# SmartHomeControllerCircuit.net
KiCad netlist of a schematic drawn in EAGLE
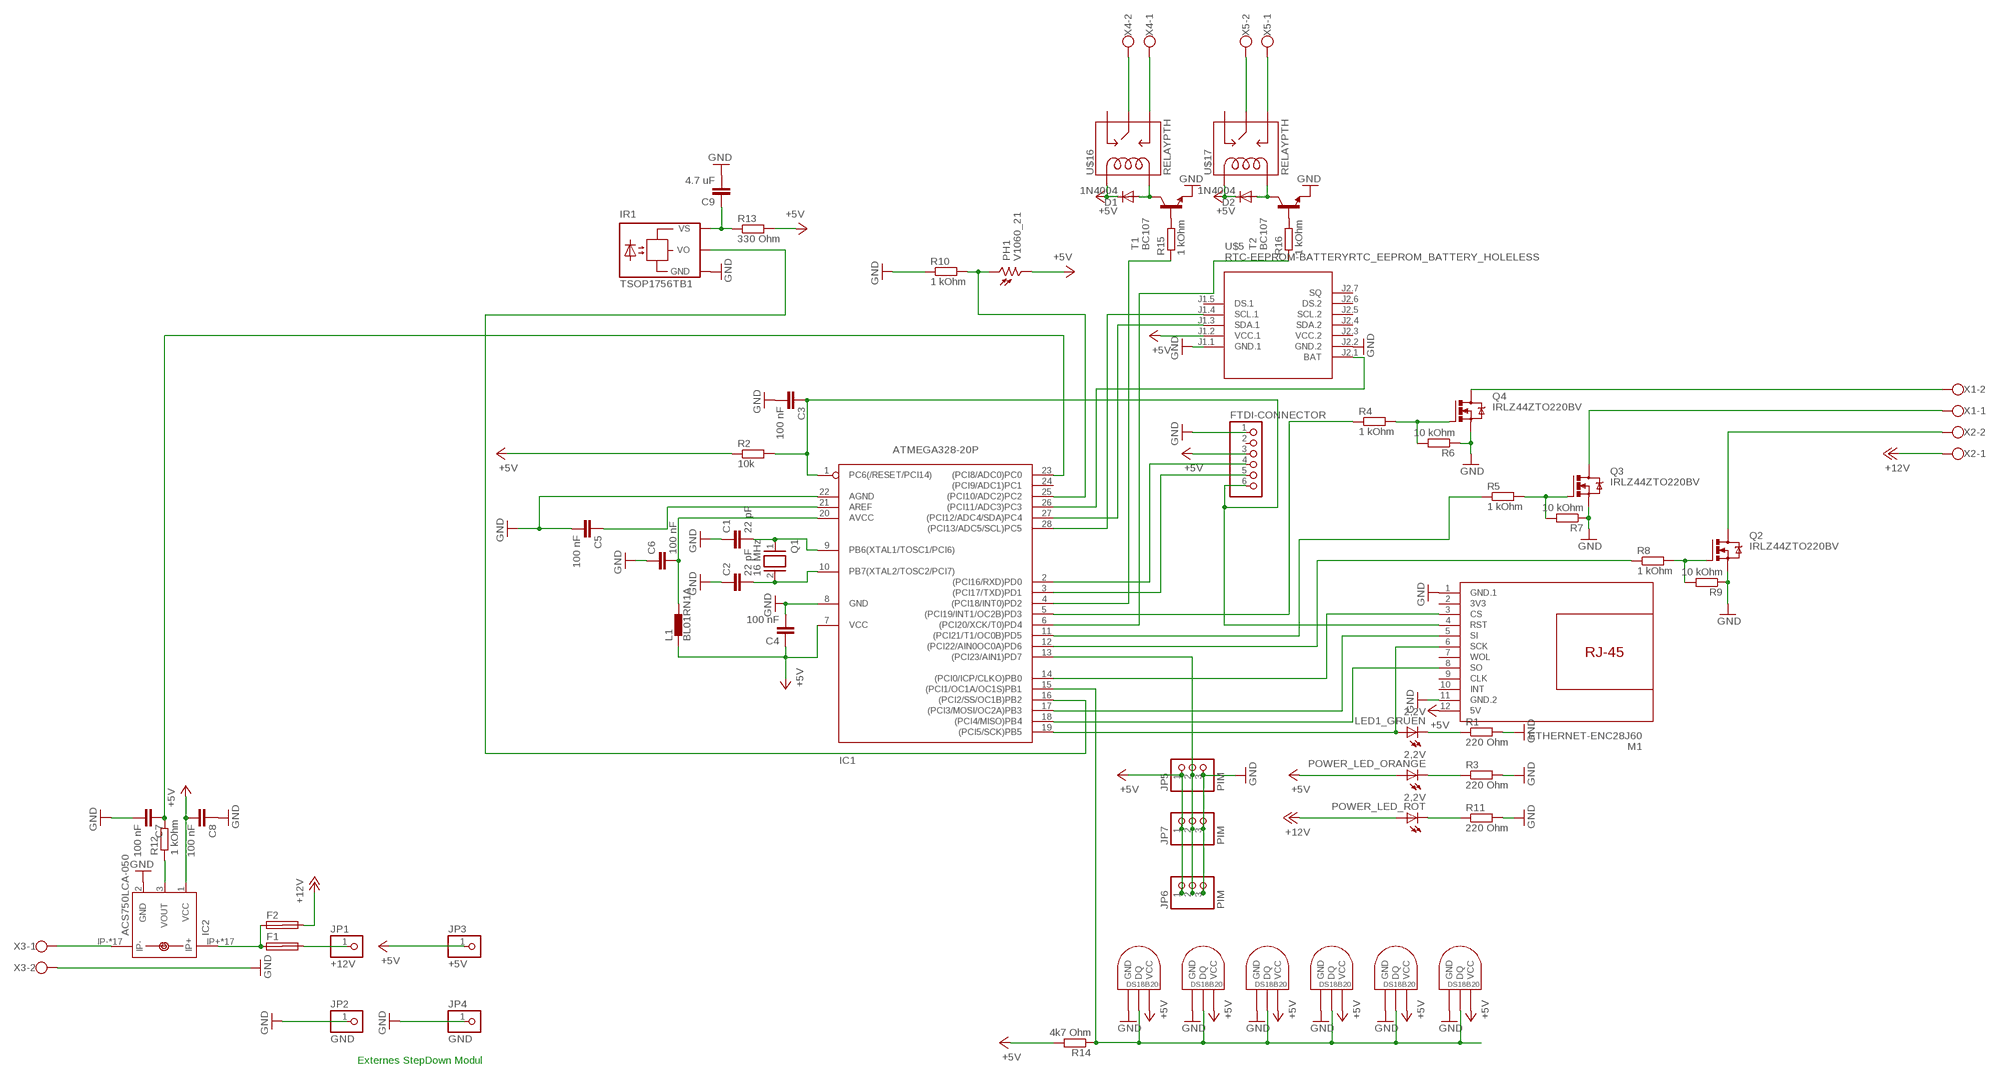
[diagram p0: schematic, sheet 1]

(export (version "E")
  (design (tool "Eeschema 10.0.6"))
  (components
    (comp (ref "C1")
      (value "22 pF")
      (footprint "eagle-import:C050-024X044")
      (libsource (lib "eagle-import") (part "C-EU050-024X044"))
    )
    (comp (ref "C2")
      (value "22 pF")
      (footprint "eagle-import:C050-024X044")
      (libsource (lib "eagle-import") (part "C-EU050-024X044"))
    )
    (comp (ref "C3")
      (value "100 nF")
      (footprint "eagle-import:C050-024X044")
      (libsource (lib "eagle-import") (part "C-EU050-024X044"))
    )
    (comp (ref "C4")
      (value "100 nF")
      (footprint "eagle-import:C050-024X044")
      (libsource (lib "eagle-import") (part "C-EU050-024X044"))
    )
    (comp (ref "C5")
      (value "100 nF")
      (footprint "eagle-import:C050-024X044")
      (libsource (lib "eagle-import") (part "C-EU050-024X044"))
    )
    (comp (ref "C6")
      (value "100 nF")
      (footprint "eagle-import:C050-024X044")
      (libsource (lib "eagle-import") (part "C-EU050-024X044"))
    )
    (comp (ref "C7")
      (value "100 nF")
      (footprint "eagle-import:C050-024X044")
      (libsource (lib "eagle-import") (part "C-EU050-024X044"))
    )
    (comp (ref "C8")
      (value "100 nF")
      (footprint "eagle-import:C050-024X044")
      (libsource (lib "eagle-import") (part "C-EU050-024X044"))
    )
    (comp (ref "C9")
      (value "4.7 uF")
      (footprint "eagle-import:C050-024X044")
      (libsource (lib "eagle-import") (part "C-EU050-024X044"))
    )
    (comp (ref "D1")
      (value "1N4004")
      (footprint "eagle-import:DO41-10")
      (libsource (lib "eagle-import") (part "1N4004"))
    )
    (comp (ref "D2")
      (value "1N4004")
      (footprint "eagle-import:DO41-10")
      (libsource (lib "eagle-import") (part "1N4004"))
    )
    (comp (ref "F1")
      (value "SH32")
      (footprint "eagle-import:SH32")
      (fields (field (name "MPN") "10207101009"))
      (libsource (lib "eagle-import") (part "SH32"))
    )
    (comp (ref "F2")
      (value "SH32")
      (footprint "eagle-import:SH32")
      (fields (field (name "MPN") "10207101009"))
      (libsource (lib "eagle-import") (part "SH32"))
    )
    (comp (ref "FTDI-CONNECTOR")
      (value "PINHD-1X6")
      (footprint "eagle-import:1X06")
      (libsource (lib "eagle-import") (part "PINHD-1X6"))
    )
    (comp (ref "IC1")
      (value "ATMEGA328-20P")
      (footprint "eagle-import:DIL28-3")
      (libsource (lib "eagle-import") (part "ATMEGA328P-20"))
    )
    (comp (ref "IC2")
      (value "ACS750LCA-050")
      (footprint "eagle-import:ACS75050")
      (fields (field (name "MF") "ALLEGRO MICROSYSTEMS, INC."))
      (libsource (lib "eagle-import") (part "ACS750CA-050L"))
    )
    (comp (ref "IR1")
      (value "TSOP1756TB1")
      (footprint "eagle-import:TSOP17_TB1")
      (libsource (lib "eagle-import") (part "TSOP17TB156"))
    )
    (comp (ref "JP1")
      (value "+12V")
      (footprint "eagle-import:1X01")
      (libsource (lib "eagle-import") (part "PINHD-1X1"))
    )
    (comp (ref "JP2")
      (value "GND")
      (footprint "eagle-import:1X01")
      (libsource (lib "eagle-import") (part "PINHD-1X1"))
    )
    (comp (ref "JP3")
      (value "+5V")
      (footprint "eagle-import:1X01")
      (libsource (lib "eagle-import") (part "PINHD-1X1"))
    )
    (comp (ref "JP4")
      (value "GND")
      (footprint "eagle-import:1X01")
      (libsource (lib "eagle-import") (part "PINHD-1X1"))
    )
    (comp (ref "JP5")
      (value "PIM")
      (footprint "eagle-import:1X03")
      (libsource (lib "eagle-import") (part "PINHD-1X3"))
    )
    (comp (ref "JP6")
      (value "PIM")
      (footprint "eagle-import:1X03")
      (libsource (lib "eagle-import") (part "PINHD-1X3"))
    )
    (comp (ref "JP7")
      (value "PIM")
      (footprint "eagle-import:1X03")
      (libsource (lib "eagle-import") (part "PINHD-1X3"))
    )
    (comp (ref "L1")
      (value "BL01RN1A")
      (footprint "eagle-import:BL01RN1A")
      (libsource (lib "eagle-import") (part "BL01RN1A"))
    )
    (comp (ref "LED1_GRUEN")
      (value "2,2V")
      (footprint "eagle-import:LED5MM")
      (libsource (lib "eagle-import") (part "LED5MM"))
    )
    (comp (ref "M1")
      (value "ETHERNET-ENC28J60")
      (footprint "eagle-import:ETHERNET-ENC28J60")
      (libsource (lib "eagle-import") (part "ETHERNET-ENC28J60"))
    )
    (comp (ref "PH1")
      (value "V1060_21")
      (footprint "eagle-import:TO-5_V10")
      (libsource (lib "eagle-import") (part "?1060V_21"))
    )
    (comp (ref "POWER_LED_ORANGE")
      (value "2,2V")
      (footprint "eagle-import:LED5MM")
      (libsource (lib "eagle-import") (part "LED5MM"))
    )
    (comp (ref "POWER_LED_ROT")
      (value "2,2V")
      (footprint "eagle-import:LED5MM")
      (libsource (lib "eagle-import") (part "LED5MM"))
    )
    (comp (ref "Q1")
      (value "16 MHz")
      (footprint "eagle-import:QS")
      (libsource (lib "eagle-import") (part "XTAL/S"))
    )
    (comp (ref "Q2")
      (value "IRLZ44ZTO220BV")
      (footprint "eagle-import:TO220BV")
      (libsource (lib "eagle-import") (part "IRLZ44ZTO220BV"))
    )
    (comp (ref "Q3")
      (value "IRLZ44ZTO220BV")
      (footprint "eagle-import:TO220BV")
      (libsource (lib "eagle-import") (part "IRLZ44ZTO220BV"))
    )
    (comp (ref "Q4")
      (value "IRLZ44ZTO220BV")
      (footprint "eagle-import:TO220BV")
      (libsource (lib "eagle-import") (part "IRLZ44ZTO220BV"))
    )
    (comp (ref "R1")
      (value "220 Ohm")
      (footprint "eagle-import:0204_7")
      (libsource (lib "eagle-import") (part "resistor_R-EU_0204/7"))
    )
    (comp (ref "R2")
      (value "10k")
      (footprint "eagle-import:0204_7")
      (libsource (lib "eagle-import") (part "resistor_R-EU_0204/7"))
    )
    (comp (ref "R3")
      (value "220 Ohm")
      (footprint "eagle-import:0204_7")
      (libsource (lib "eagle-import") (part "resistor_R-EU_0204/7"))
    )
    (comp (ref "R4")
      (value "1 kOhm")
      (footprint "eagle-import:0309_12")
      (libsource (lib "eagle-import") (part "R-EU_0309/12"))
    )
    (comp (ref "R5")
      (value "1 kOhm")
      (footprint "eagle-import:0309_12")
      (libsource (lib "eagle-import") (part "R-EU_0309/12"))
    )
    (comp (ref "R6")
      (value "10 kOhm")
      (footprint "eagle-import:0309_12")
      (libsource (lib "eagle-import") (part "R-EU_0309/12"))
    )
    (comp (ref "R7")
      (value "10 kOhm")
      (footprint "eagle-import:0309_12")
      (libsource (lib "eagle-import") (part "R-EU_0309/12"))
    )
    (comp (ref "R8")
      (value "1 kOhm")
      (footprint "eagle-import:0309_12")
      (libsource (lib "eagle-import") (part "R-EU_0309/12"))
    )
    (comp (ref "R9")
      (value "10 kOhm")
      (footprint "eagle-import:0309_12")
      (libsource (lib "eagle-import") (part "R-EU_0309/12"))
    )
    (comp (ref "R10")
      (value "1 kOhm")
      (footprint "eagle-import:0309_12")
      (libsource (lib "eagle-import") (part "R-EU_0309/12"))
    )
    (comp (ref "R11")
      (value "220 Ohm")
      (footprint "eagle-import:0204_7")
      (libsource (lib "eagle-import") (part "resistor_R-EU_0204/7"))
    )
    (comp (ref "R12")
      (value "1 kOhm")
      (footprint "eagle-import:0204_7")
      (libsource (lib "eagle-import") (part "resistor_R-EU_0204/7"))
    )
    (comp (ref "R13")
      (value "330 Ohm")
      (footprint "eagle-import:0309_12")
      (libsource (lib "eagle-import") (part "R-EU_0309/12"))
    )
    (comp (ref "R14")
      (value "4k7 Ohm")
      (footprint "eagle-import:0204_7")
      (libsource (lib "eagle-import") (part "resistor_R-EU_0204/7"))
    )
    (comp (ref "R15")
      (value "1 kOhm")
      (footprint "eagle-import:0309_12")
      (libsource (lib "eagle-import") (part "R-EU_0309/12"))
    )
    (comp (ref "R16")
      (value "1 kOhm")
      (footprint "eagle-import:0309_12")
      (libsource (lib "eagle-import") (part "R-EU_0309/12"))
    )
    (comp (ref "T1")
      (value "BC107")
      (footprint "eagle-import:TO18")
      (libsource (lib "eagle-import") (part "BC107"))
    )
    (comp (ref "T2")
      (value "BC107")
      (footprint "eagle-import:TO18")
      (libsource (lib "eagle-import") (part "BC107"))
    )
    (comp (ref "U$5")
      (value "RTC-EEPROM-BATTERYRTC_EEPROM_BATTERY_HOLELESS")
      (footprint "eagle-import:RTC_EEPROM_BATTERY")
      (libsource (lib "eagle-import") (part "RTC-EEPROM-BATTERYRTC_EEPROM_BATTERY_HOLELESS"))
    )
    (comp (ref "U$10")
      (value "DS1820TO92")
      (footprint "eagle-import:DS1820")
      (libsource (lib "eagle-import") (part "DS1820TO92"))
    )
    (comp (ref "U$11")
      (value "DS1820TO92")
      (footprint "eagle-import:DS1820")
      (libsource (lib "eagle-import") (part "DS1820TO92"))
    )
    (comp (ref "U$12")
      (value "DS1820TO92")
      (footprint "eagle-import:DS1820")
      (libsource (lib "eagle-import") (part "DS1820TO92"))
    )
    (comp (ref "U$13")
      (value "DS1820TO92")
      (footprint "eagle-import:DS1820")
      (libsource (lib "eagle-import") (part "DS1820TO92"))
    )
    (comp (ref "U$14")
      (value "DS1820TO92")
      (footprint "eagle-import:DS1820")
      (libsource (lib "eagle-import") (part "DS1820TO92"))
    )
    (comp (ref "U$15")
      (value "DS1820TO92")
      (footprint "eagle-import:DS1820")
      (libsource (lib "eagle-import") (part "DS1820TO92"))
    )
    (comp (ref "U$16")
      (value "RELAYPTH")
      (footprint "eagle-import:SRD-05VDC-SL-C")
      (libsource (lib "eagle-import") (part "RELAYPTH"))
    )
    (comp (ref "U$17")
      (value "RELAYPTH")
      (footprint "eagle-import:SRD-05VDC-SL-C")
      (libsource (lib "eagle-import") (part "RELAYPTH"))
    )
    (comp (ref "X1")
      (value "W237-102")
      (footprint "eagle-import:W237-102")
      (fields (field (name "MPN") "237-102"))
      (libsource (lib "eagle-import") (part "W237-102"))
    )
    (comp (ref "X2")
      (value "W237-102")
      (footprint "eagle-import:W237-102")
      (fields (field (name "MPN") "237-102"))
      (libsource (lib "eagle-import") (part "W237-102"))
    )
    (comp (ref "X3")
      (value "W237-102")
      (footprint "eagle-import:W237-102")
      (fields (field (name "MPN") "237-102"))
      (libsource (lib "eagle-import") (part "W237-102"))
    )
    (comp (ref "X4")
      (value "W237-102")
      (footprint "eagle-import:W237-102")
      (fields (field (name "MPN") "237-102"))
      (libsource (lib "eagle-import") (part "W237-102"))
    )
    (comp (ref "X5")
      (value "W237-102")
      (footprint "eagle-import:W237-102")
      (fields (field (name "MPN") "237-102"))
      (libsource (lib "eagle-import") (part "W237-102"))
    )
  )
  (nets
    (net (code "1") (name "+5V") (class "Default")
      (node (ref "C4") (pin "1") (pinfunction "1_1") (pintype "passive"))
      (node (ref "C8") (pin "2") (pinfunction "2_2") (pintype "passive"))
      (node (ref "D1") (pin "C") (pinfunction "C_C") (pintype "passive"))
      (node (ref "D2") (pin "C") (pinfunction "C_C") (pintype "passive"))
      (node (ref "FTDI-CONNECTOR") (pin "3") (pinfunction "3_3") (pintype "passive"))
      (node (ref "IC1") (pin "7") (pinfunction "VCC_7") (pintype "bidirectional"))
      (node (ref "IC2") (pin "1") (pinfunction "VCC_1") (pintype "power_in"))
      (node (ref "JP3") (pin "1") (pinfunction "1_1") (pintype "passive"))
      (node (ref "JP5") (pin "1") (pinfunction "1_1") (pintype "passive"))
      (node (ref "JP6") (pin "1") (pinfunction "1_1") (pintype "passive"))
      (node (ref "JP7") (pin "1") (pinfunction "1_1") (pintype "passive"))
      (node (ref "L1") (pin "1") (pinfunction "1_1") (pintype "passive"))
      (node (ref "M1") (pin "12") (pinfunction "5V_12") (pintype "power_in"))
      (node (ref "PH1") (pin "2") (pinfunction "2_2") (pintype "passive"))
      (node (ref "POWER_LED_ORANGE") (pin "A") (pinfunction "A_A") (pintype "passive"))
      (node (ref "R13") (pin "2") (pinfunction "2_2") (pintype "passive"))
      (node (ref "R14") (pin "2") (pinfunction "2_2") (pintype "passive"))
      (node (ref "R2") (pin "1") (pinfunction "1_1") (pintype "passive"))
      (node (ref "U$10") (pin "VDD") (pinfunction "VCC_VDD") (pintype "power_in"))
      (node (ref "U$11") (pin "VDD") (pinfunction "VCC_VDD") (pintype "power_in"))
      (node (ref "U$12") (pin "VDD") (pinfunction "VCC_VDD") (pintype "power_in"))
      (node (ref "U$13") (pin "VDD") (pinfunction "VCC_VDD") (pintype "power_in"))
      (node (ref "U$14") (pin "VDD") (pinfunction "VCC_VDD") (pintype "power_in"))
      (node (ref "U$15") (pin "VDD") (pinfunction "VCC_VDD") (pintype "power_in"))
      (node (ref "U$16") (pin "COIL1") (pinfunction "COIL1_COIL1") (pintype "bidirectional"))
      (node (ref "U$17") (pin "COIL1") (pinfunction "COIL1_COIL1") (pintype "bidirectional"))
      (node (ref "U$5") (pin "J1.2") (pinfunction "VCC.1_J1.2") (pintype "power_in"))
    )
    (net (code "2") (name "+12V") (class "Default")
      (node (ref "F2") (pin "2A") (pinfunction "2A_2A") (pintype "passive"))
      (node (ref "POWER_LED_ROT") (pin "A") (pinfunction "A_A") (pintype "passive"))
      (node (ref "X2") (pin "1") (pinfunction "KL_1") (pintype "passive"))
    )
    (net (code "3") (name "/+12V_IN") (class "Default")
      (node (ref "F1") (pin "1A") (pinfunction "1A_1A") (pintype "passive"))
      (node (ref "F2") (pin "1A") (pinfunction "1A_1A") (pintype "passive"))
      (node (ref "IC2") (pin "IP+") (pinfunction "IP+_IP+") (pintype "passive"))
      (node (ref "IC2") (pin "IP+@10") (pinfunction "IP+_IP+@10") (pintype "passive"))
      (node (ref "IC2") (pin "IP+@11") (pinfunction "IP+_IP+@11") (pintype "passive"))
      (node (ref "IC2") (pin "IP+@12") (pinfunction "IP+_IP+@12") (pintype "passive"))
      (node (ref "IC2") (pin "IP+@13") (pinfunction "IP+_IP+@13") (pintype "passive"))
      (node (ref "IC2") (pin "IP+@14") (pinfunction "IP+_IP+@14") (pintype "passive"))
      (node (ref "IC2") (pin "IP+@15") (pinfunction "IP+_IP+@15") (pintype "passive"))
      (node (ref "IC2") (pin "IP+@16") (pinfunction "IP+_IP+@16") (pintype "passive"))
      (node (ref "IC2") (pin "IP+@17") (pinfunction "IP+_IP+@17") (pintype "passive"))
      (node (ref "IC2") (pin "IP+@2") (pinfunction "IP+_IP+@2") (pintype "passive"))
      (node (ref "IC2") (pin "IP+@3") (pinfunction "IP+_IP+@3") (pintype "passive"))
      (node (ref "IC2") (pin "IP+@4") (pinfunction "IP+_IP+@4") (pintype "passive"))
      (node (ref "IC2") (pin "IP+@5") (pinfunction "IP+_IP+@5") (pintype "passive"))
      (node (ref "IC2") (pin "IP+@6") (pinfunction "IP+_IP+@6") (pintype "passive"))
      (node (ref "IC2") (pin "IP+@7") (pinfunction "IP+_IP+@7") (pintype "passive"))
      (node (ref "IC2") (pin "IP+@8") (pinfunction "IP+_IP+@8") (pintype "passive"))
      (node (ref "IC2") (pin "IP+@9") (pinfunction "IP+_IP+@9") (pintype "passive"))
      (node (ref "IC2") (pin "IP-") (pinfunction "IP-_IP-") (pintype "passive"))
      (node (ref "IC2") (pin "IP-@10") (pinfunction "IP-_IP-@10") (pintype "passive"))
      (node (ref "IC2") (pin "IP-@11") (pinfunction "IP-_IP-@11") (pintype "passive"))
      (node (ref "IC2") (pin "IP-@12") (pinfunction "IP-_IP-@12") (pintype "passive"))
      (node (ref "IC2") (pin "IP-@13") (pinfunction "IP-_IP-@13") (pintype "passive"))
      (node (ref "IC2") (pin "IP-@14") (pinfunction "IP-_IP-@14") (pintype "passive"))
      (node (ref "IC2") (pin "IP-@15") (pinfunction "IP-_IP-@15") (pintype "passive"))
      (node (ref "IC2") (pin "IP-@16") (pinfunction "IP-_IP-@16") (pintype "passive"))
      (node (ref "IC2") (pin "IP-@17") (pinfunction "IP-_IP-@17") (pintype "passive"))
      (node (ref "IC2") (pin "IP-@2") (pinfunction "IP-_IP-@2") (pintype "passive"))
      (node (ref "IC2") (pin "IP-@3") (pinfunction "IP-_IP-@3") (pintype "passive"))
      (node (ref "IC2") (pin "IP-@4") (pinfunction "IP-_IP-@4") (pintype "passive"))
      (node (ref "IC2") (pin "IP-@5") (pinfunction "IP-_IP-@5") (pintype "passive"))
      (node (ref "IC2") (pin "IP-@6") (pinfunction "IP-_IP-@6") (pintype "passive"))
      (node (ref "IC2") (pin "IP-@7") (pinfunction "IP-_IP-@7") (pintype "passive"))
      (node (ref "IC2") (pin "IP-@8") (pinfunction "IP-_IP-@8") (pintype "passive"))
      (node (ref "IC2") (pin "IP-@9") (pinfunction "IP-_IP-@9") (pintype "passive"))
      (node (ref "X3") (pin "1") (pinfunction "KL_1") (pintype "passive"))
    )
    (net (code "4") (name "/3V3") (class "Default")
      (node (ref "M1") (pin "2") (pinfunction "3V3_2") (pintype "power_in"))
    )
    (net (code "5") (name "/VCC.2") (class "Default")
      (node (ref "U$5") (pin "J2.3") (pinfunction "VCC.2_J2.3") (pintype "power_in"))
    )
    (net (code "6") (name "GND") (class "Default")
      (node (ref "C1") (pin "1") (pinfunction "1_1") (pintype "passive"))
      (node (ref "C2") (pin "1") (pinfunction "1_1") (pintype "passive"))
      (node (ref "C3") (pin "2") (pinfunction "2_2") (pintype "passive"))
      (node (ref "C4") (pin "2") (pinfunction "2_2") (pintype "passive"))
      (node (ref "C5") (pin "2") (pinfunction "2_2") (pintype "passive"))
      (node (ref "C6") (pin "1") (pinfunction "1_1") (pintype "passive"))
      (node (ref "C7") (pin "2") (pinfunction "2_2") (pintype "passive"))
      (node (ref "C8") (pin "1") (pinfunction "1_1") (pintype "passive"))
      (node (ref "C9") (pin "2") (pinfunction "2_2") (pintype "passive"))
      (node (ref "FTDI-CONNECTOR") (pin "1") (pinfunction "1_1") (pintype "passive"))
      (node (ref "IC1") (pin "22") (pinfunction "AGND_22") (pintype "bidirectional"))
      (node (ref "IC1") (pin "8") (pinfunction "GND_8") (pintype "bidirectional"))
      (node (ref "IC2") (pin "2") (pinfunction "GND_2") (pintype "power_in"))
      (node (ref "IR1") (pin "GND") (pinfunction "GND_GND") (pintype "power_in"))
      (node (ref "JP2") (pin "1") (pinfunction "1_1") (pintype "passive"))
      (node (ref "JP4") (pin "1") (pinfunction "1_1") (pintype "passive"))
      (node (ref "JP5") (pin "3") (pinfunction "3_3") (pintype "passive"))
      (node (ref "JP6") (pin "3") (pinfunction "3_3") (pintype "passive"))
      (node (ref "JP7") (pin "3") (pinfunction "3_3") (pintype "passive"))
      (node (ref "M1") (pin "1") (pinfunction "GND.1_1") (pintype "power_in"))
      (node (ref "M1") (pin "11") (pinfunction "GND.2_11") (pintype "power_in"))
      (node (ref "Q2") (pin "S") (pinfunction "S_S") (pintype "passive"))
      (node (ref "Q3") (pin "S") (pinfunction "S_S") (pintype "passive"))
      (node (ref "Q4") (pin "S") (pinfunction "S_S") (pintype "passive"))
      (node (ref "R1") (pin "2") (pinfunction "2_2") (pintype "passive"))
      (node (ref "R10") (pin "1") (pinfunction "1_1") (pintype "passive"))
      (node (ref "R11") (pin "2") (pinfunction "2_2") (pintype "passive"))
      (node (ref "R3") (pin "2") (pinfunction "2_2") (pintype "passive"))
      (node (ref "R6") (pin "1") (pinfunction "1_1") (pintype "passive"))
      (node (ref "R7") (pin "1") (pinfunction "1_1") (pintype "passive"))
      (node (ref "R9") (pin "1") (pinfunction "1_1") (pintype "passive"))
      (node (ref "T1") (pin "1") (pinfunction "E_1") (pintype "passive"))
      (node (ref "T2") (pin "1") (pinfunction "E_1") (pintype "passive"))
      (node (ref "U$10") (pin "GND") (pinfunction "GND_GND") (pintype "power_in"))
      (node (ref "U$11") (pin "GND") (pinfunction "GND_GND") (pintype "power_in"))
      (node (ref "U$12") (pin "GND") (pinfunction "GND_GND") (pintype "power_in"))
      (node (ref "U$13") (pin "GND") (pinfunction "GND_GND") (pintype "power_in"))
      (node (ref "U$14") (pin "GND") (pinfunction "GND_GND") (pintype "power_in"))
      (node (ref "U$15") (pin "GND") (pinfunction "GND_GND") (pintype "power_in"))
      (node (ref "U$5") (pin "J1.1") (pinfunction "GND.1_J1.1") (pintype "power_in"))
      (node (ref "U$5") (pin "J2.2") (pinfunction "GND.2_J2.2") (pintype "power_in"))
      (node (ref "X3") (pin "2") (pinfunction "KL_2") (pintype "passive"))
    )
    (net (code "7") (name "Net-(C9-Pad1)") (class "Default")
      (node (ref "C9") (pin "1") (pinfunction "1_1") (pintype "passive"))
      (node (ref "IR1") (pin "VS") (pinfunction "VS_VS") (pintype "power_in"))
      (node (ref "R13") (pin "1") (pinfunction "1_1") (pintype "passive"))
    )
    (net (code "8") (name "Net-(F1-Pad2A)") (class "Default")
      (node (ref "F1") (pin "2A") (pinfunction "2A_2A") (pintype "passive"))
      (node (ref "JP1") (pin "1") (pinfunction "1_1") (pintype "passive"))
    )
    (net (code "9") (name "Net-(IC1-(PCI0{slash}ICP{slash}CLKO)PB0)") (class "Default")
      (node (ref "IC1") (pin "14") (pinfunction "(PCI0/ICP/CLKO)PB0_14") (pintype "bidirectional"))
      (node (ref "M1") (pin "3") (pinfunction "CS_3") (pintype "bidirectional"))
    )
    (net (code "10") (name "Net-(IC1-(PCI1{slash}OC1A{slash}OC1S)PB1)") (class "Default")
      (node (ref "IC1") (pin "15") (pinfunction "(PCI1/OC1A/OC1S)PB1_15") (pintype "bidirectional"))
      (node (ref "R14") (pin "1") (pinfunction "1_1") (pintype "passive"))
      (node (ref "U$10") (pin "DQ") (pinfunction "DQ_DQ") (pintype "bidirectional"))
      (node (ref "U$11") (pin "DQ") (pinfunction "DQ_DQ") (pintype "bidirectional"))
      (node (ref "U$12") (pin "DQ") (pinfunction "DQ_DQ") (pintype "bidirectional"))
      (node (ref "U$13") (pin "DQ") (pinfunction "DQ_DQ") (pintype "bidirectional"))
      (node (ref "U$14") (pin "DQ") (pinfunction "DQ_DQ") (pintype "bidirectional"))
      (node (ref "U$15") (pin "DQ") (pinfunction "DQ_DQ") (pintype "bidirectional"))
    )
    (net (code "11") (name "Net-(IC1-(PCI2{slash}SS{slash}OC1B)PB2)") (class "Default")
      (node (ref "IC1") (pin "16") (pinfunction "(PCI2/SS/OC1B)PB2_16") (pintype "bidirectional"))
      (node (ref "IR1") (pin "VO") (pinfunction "VO_VO") (pintype "open_collector"))
    )
    (net (code "12") (name "Net-(IC1-(PCI3{slash}MOSI{slash}OC2A)PB3)") (class "Default")
      (node (ref "IC1") (pin "17") (pinfunction "(PCI3/MOSI/OC2A)PB3_17") (pintype "bidirectional"))
      (node (ref "M1") (pin "5") (pinfunction "SI_5") (pintype "bidirectional"))
    )
    (net (code "13") (name "Net-(IC1-(PCI4{slash}MISO)PB4)") (class "Default")
      (node (ref "IC1") (pin "18") (pinfunction "(PCI4/MISO)PB4_18") (pintype "bidirectional"))
      (node (ref "M1") (pin "8") (pinfunction "SO_8") (pintype "bidirectional"))
    )
    (net (code "14") (name "Net-(IC1-(PCI5{slash}SCK)PB5)") (class "Default")
      (node (ref "IC1") (pin "19") (pinfunction "(PCI5/SCK)PB5_19") (pintype "bidirectional"))
      (node (ref "LED1_GRUEN") (pin "A") (pinfunction "A_A") (pintype "passive"))
      (node (ref "M1") (pin "6") (pinfunction "SCK_6") (pintype "bidirectional"))
    )
    (net (code "15") (name "Net-(IC1-(PCI8{slash}ADC0)PC0)") (class "Default")
      (node (ref "C7") (pin "1") (pinfunction "1_1") (pintype "passive"))
      (node (ref "IC1") (pin "23") (pinfunction "(PCI8/ADC0)PC0_23") (pintype "bidirectional"))
      (node (ref "R12") (pin "2") (pinfunction "2_2") (pintype "passive"))
    )
    (net (code "16") (name "Net-(IC1-(PCI10{slash}ADC2)PC2)") (class "Default")
      (node (ref "IC1") (pin "25") (pinfunction "(PCI10/ADC2)PC2_25") (pintype "bidirectional"))
      (node (ref "PH1") (pin "1") (pinfunction "1_1") (pintype "passive"))
      (node (ref "R10") (pin "2") (pinfunction "2_2") (pintype "passive"))
    )
    (net (code "17") (name "Net-(IC1-(PCI11{slash}ADC3)PC3)") (class "Default")
      (node (ref "IC1") (pin "26") (pinfunction "(PCI11/ADC3)PC3_26") (pintype "bidirectional"))
      (node (ref "U$5") (pin "J2.1") (pinfunction "BAT_J2.1") (pintype "bidirectional"))
    )
    (net (code "18") (name "Net-(IC1-(PCI12{slash}ADC4{slash}SDA)PC4)") (class "Default")
      (node (ref "IC1") (pin "27") (pinfunction "(PCI12/ADC4/SDA)PC4_27") (pintype "bidirectional"))
      (node (ref "U$5") (pin "J1.3") (pinfunction "SDA.1_J1.3") (pintype "bidirectional"))
    )
    (net (code "19") (name "Net-(IC1-(PCI13{slash}ADC5{slash}SCL)PC5)") (class "Default")
      (node (ref "IC1") (pin "28") (pinfunction "(PCI13/ADC5/SCL)PC5_28") (pintype "bidirectional"))
      (node (ref "U$5") (pin "J1.4") (pinfunction "SCL.1_J1.4") (pintype "bidirectional"))
    )
    (net (code "20") (name "Net-(IC1-(PCI16{slash}RXD)PD0)") (class "Default")
      (node (ref "FTDI-CONNECTOR") (pin "4") (pinfunction "4_4") (pintype "passive"))
      (node (ref "IC1") (pin "2") (pinfunction "(PCI16/RXD)PD0_2") (pintype "bidirectional"))
    )
    (net (code "21") (name "Net-(IC1-(PCI17{slash}TXD)PD1)") (class "Default")
      (node (ref "FTDI-CONNECTOR") (pin "5") (pinfunction "5_5") (pintype "passive"))
      (node (ref "IC1") (pin "3") (pinfunction "(PCI17/TXD)PD1_3") (pintype "bidirectional"))
    )
    (net (code "22") (name "Net-(IC1-(PCI18{slash}INT0)PD2)") (class "Default")
      (node (ref "IC1") (pin "4") (pinfunction "(PCI18/INT0)PD2_4") (pintype "bidirectional"))
      (node (ref "R15") (pin "1") (pinfunction "1_1") (pintype "passive"))
    )
    (net (code "23") (name "Net-(IC1-(PCI19{slash}INT1{slash}OC2B)PD3)") (class "Default")
      (node (ref "IC1") (pin "5") (pinfunction "(PCI19/INT1/OC2B)PD3_5") (pintype "bidirectional"))
      (node (ref "R4") (pin "1") (pinfunction "1_1") (pintype "passive"))
    )
    (net (code "24") (name "Net-(IC1-(PCI20{slash}XCK{slash}T0)PD4)") (class "Default")
      (node (ref "IC1") (pin "6") (pinfunction "(PCI20/XCK/T0)PD4_6") (pintype "bidirectional"))
      (node (ref "R16") (pin "1") (pinfunction "1_1") (pintype "passive"))
    )
    (net (code "25") (name "Net-(IC1-(PCI21{slash}T1{slash}OC0B)PD5)") (class "Default")
      (node (ref "IC1") (pin "11") (pinfunction "(PCI21/T1/OC0B)PD5_11") (pintype "bidirectional"))
      (node (ref "R5") (pin "1") (pinfunction "1_1") (pintype "passive"))
    )
    (net (code "26") (name "Net-(IC1-(PCI22{slash}AIN0OC0A)PD6)") (class "Default")
      (node (ref "IC1") (pin "12") (pinfunction "(PCI22/AIN0OC0A)PD6_12") (pintype "bidirectional"))
      (node (ref "R8") (pin "1") (pinfunction "1_1") (pintype "passive"))
    )
    (net (code "27") (name "Net-(IC1-(PCI23{slash}AIN1)PD7)") (class "Default")
      (node (ref "IC1") (pin "13") (pinfunction "(PCI23/AIN1)PD7_13") (pintype "bidirectional"))
      (node (ref "JP5") (pin "2") (pinfunction "2_2") (pintype "passive"))
      (node (ref "JP6") (pin "2") (pinfunction "2_2") (pintype "passive"))
      (node (ref "JP7") (pin "2") (pinfunction "2_2") (pintype "passive"))
    )
    (net (code "28") (name "Net-(IC1-AREF)") (class "Default")
      (node (ref "C5") (pin "1") (pinfunction "1_1") (pintype "passive"))
      (node (ref "IC1") (pin "21") (pinfunction "AREF_21") (pintype "bidirectional"))
    )
    (net (code "29") (name "Net-(IC1-AVCC)") (class "Default")
      (node (ref "C6") (pin "2") (pinfunction "2_2") (pintype "passive"))
      (node (ref "IC1") (pin "20") (pinfunction "AVCC_20") (pintype "bidirectional"))
      (node (ref "L1") (pin "2") (pinfunction "2_2") (pintype "passive"))
    )
    (net (code "30") (name "Net-(IC1-PB6(XTAL1{slash}TOSC1{slash}PCI6))") (class "Default")
      (node (ref "C1") (pin "2") (pinfunction "2_2") (pintype "passive"))
      (node (ref "IC1") (pin "9") (pinfunction "PB6(XTAL1/TOSC1/PCI6)_9") (pintype "bidirectional"))
      (node (ref "Q1") (pin "1") (pinfunction "1_1") (pintype "passive"))
    )
    (net (code "31") (name "Net-(IC1-PB7(XTAL2{slash}TOSC2{slash}PCI7))") (class "Default")
      (node (ref "C2") (pin "2") (pinfunction "2_2") (pintype "passive"))
      (node (ref "IC1") (pin "10") (pinfunction "PB7(XTAL2/TOSC2/PCI7)_10") (pintype "bidirectional"))
      (node (ref "Q1") (pin "2") (pinfunction "2_2") (pintype "passive"))
    )
    (net (code "32") (name "Net-(IC1-PC6({slash}RESET{slash}PCI14))") (class "Default")
      (node (ref "C3") (pin "1") (pinfunction "1_1") (pintype "passive"))
      (node (ref "FTDI-CONNECTOR") (pin "6") (pinfunction "6_6") (pintype "passive"))
      (node (ref "IC1") (pin "1") (pinfunction "PC6(/RESET/PCI14)_1") (pintype "bidirectional"))
      (node (ref "M1") (pin "4") (pinfunction "RST_4") (pintype "bidirectional"))
      (node (ref "R2") (pin "2") (pinfunction "2_2") (pintype "passive"))
    )
    (net (code "33") (name "Net-(IC2-VOUT)") (class "Default")
      (node (ref "IC2") (pin "3") (pinfunction "VOUT_3") (pintype "output"))
      (node (ref "R12") (pin "1") (pinfunction "1_1") (pintype "passive"))
    )
    (net (code "34") (name "Net-(LED1_GRUEN-C)") (class "Default")
      (node (ref "LED1_GRUEN") (pin "K") (pinfunction "C_K") (pintype "passive"))
      (node (ref "R1") (pin "1") (pinfunction "1_1") (pintype "passive"))
    )
    (net (code "35") (name "Net-(POWER_LED_ORANGE-C)") (class "Default")
      (node (ref "POWER_LED_ORANGE") (pin "K") (pinfunction "C_K") (pintype "passive"))
      (node (ref "R3") (pin "1") (pinfunction "1_1") (pintype "passive"))
    )
    (net (code "36") (name "Net-(POWER_LED_ROT-C)") (class "Default")
      (node (ref "POWER_LED_ROT") (pin "K") (pinfunction "C_K") (pintype "passive"))
      (node (ref "R11") (pin "1") (pinfunction "1_1") (pintype "passive"))
    )
    (net (code "37") (name "Net-(Q2-PadG)") (class "Default")
      (node (ref "Q2") (pin "G") (pinfunction "G_G") (pintype "passive"))
      (node (ref "R8") (pin "2") (pinfunction "2_2") (pintype "passive"))
      (node (ref "R9") (pin "2") (pinfunction "2_2") (pintype "passive"))
    )
    (net (code "38") (name "Net-(Q3-PadG)") (class "Default")
      (node (ref "Q3") (pin "G") (pinfunction "G_G") (pintype "passive"))
      (node (ref "R5") (pin "2") (pinfunction "2_2") (pintype "passive"))
      (node (ref "R7") (pin "2") (pinfunction "2_2") (pintype "passive"))
    )
    (net (code "39") (name "Net-(Q4-PadG)") (class "Default")
      (node (ref "Q4") (pin "G") (pinfunction "G_G") (pintype "passive"))
      (node (ref "R4") (pin "2") (pinfunction "2_2") (pintype "passive"))
      (node (ref "R6") (pin "2") (pinfunction "2_2") (pintype "passive"))
    )
    (net (code "40") (name "Net-(T1-B)") (class "Default")
      (node (ref "R15") (pin "2") (pinfunction "2_2") (pintype "passive"))
      (node (ref "T1") (pin "2") (pinfunction "B_2") (pintype "passive"))
    )
    (net (code "41") (name "Net-(T1-C)") (class "Default")
      (node (ref "D1") (pin "A") (pinfunction "A_A") (pintype "passive"))
      (node (ref "T1") (pin "3") (pinfunction "C_3") (pintype "passive"))
      (node (ref "U$16") (pin "COIL0") (pinfunction "COIL0_COIL0") (pintype "bidirectional"))
    )
    (net (code "42") (name "Net-(T2-B)") (class "Default")
      (node (ref "R16") (pin "2") (pinfunction "2_2") (pintype "passive"))
      (node (ref "T2") (pin "2") (pinfunction "B_2") (pintype "passive"))
    )
    (net (code "43") (name "Net-(T2-C)") (class "Default")
      (node (ref "D2") (pin "A") (pinfunction "A_A") (pintype "passive"))
      (node (ref "T2") (pin "3") (pinfunction "C_3") (pintype "passive"))
      (node (ref "U$17") (pin "COIL0") (pinfunction "COIL0_COIL0") (pintype "bidirectional"))
    )
    (net (code "44") (name "Net-(X1A-KL)") (class "Default")
      (node (ref "Q3") (pin "D") (pinfunction "D_D") (pintype "passive"))
      (node (ref "X1") (pin "1") (pinfunction "KL_1") (pintype "passive"))
    )
    (net (code "45") (name "Net-(X1B-KL)") (class "Default")
      (node (ref "Q4") (pin "D") (pinfunction "D_D") (pintype "passive"))
      (node (ref "X1") (pin "2") (pinfunction "KL_2") (pintype "passive"))
    )
    (net (code "46") (name "Net-(X2B-KL)") (class "Default")
      (node (ref "Q2") (pin "D") (pinfunction "D_D") (pintype "passive"))
      (node (ref "X2") (pin "2") (pinfunction "KL_2") (pintype "passive"))
    )
    (net (code "47") (name "Net-(X4A-KL)") (class "Default")
      (node (ref "U$16") (pin "SWOPEN") (pinfunction "SWOPEN_SWOPEN") (pintype "bidirectional"))
      (node (ref "X4") (pin "1") (pinfunction "KL_1") (pintype "passive"))
    )
    (net (code "48") (name "Net-(X4B-KL)") (class "Default")
      (node (ref "U$16") (pin "SWCOMMON") (pinfunction "SWCOMMON_SWCOMMON") (pintype "bidirectional"))
      (node (ref "X4") (pin "2") (pinfunction "KL_2") (pintype "passive"))
    )
    (net (code "49") (name "Net-(X5A-KL)") (class "Default")
      (node (ref "U$17") (pin "SWOPEN") (pinfunction "SWOPEN_SWOPEN") (pintype "bidirectional"))
      (node (ref "X5") (pin "1") (pinfunction "KL_1") (pintype "passive"))
    )
    (net (code "50") (name "Net-(X5B-KL)") (class "Default")
      (node (ref "U$17") (pin "SWCOMMON") (pinfunction "SWCOMMON_SWCOMMON") (pintype "bidirectional"))
      (node (ref "X5") (pin "2") (pinfunction "KL_2") (pintype "passive"))
    )
    (net (code "51") (name "unconnected-(F1-Pad1B)") (class "Default")
      (node (ref "F1") (pin "1B") (pinfunction "1B_1B") (pintype "passive"))
    )
    (net (code "52") (name "unconnected-(F1-Pad2B)") (class "Default")
      (node (ref "F1") (pin "2B") (pinfunction "2B_2B") (pintype "passive"))
    )
    (net (code "53") (name "unconnected-(F2-Pad1B)") (class "Default")
      (node (ref "F2") (pin "1B") (pinfunction "1B_1B") (pintype "passive"))
    )
    (net (code "54") (name "unconnected-(F2-Pad2B)") (class "Default")
      (node (ref "F2") (pin "2B") (pinfunction "2B_2B") (pintype "passive"))
    )
    (net (code "55") (name "unconnected-(FTDI-CONNECTOR-Pad2)") (class "Default")
      (node (ref "FTDI-CONNECTOR") (pin "2") (pinfunction "2_2") (pintype "passive"))
    )
    (net (code "56") (name "unconnected-(IC1-(PCI9{slash}ADC1)PC1-Pad24)") (class "Default")
      (node (ref "IC1") (pin "24") (pinfunction "(PCI9/ADC1)PC1_24") (pintype "bidirectional"))
    )
    (net (code "57") (name "unconnected-(M1-CLK-Pad9)") (class "Default")
      (node (ref "M1") (pin "9") (pinfunction "CLK_9") (pintype "bidirectional"))
    )
    (net (code "58") (name "unconnected-(M1-INT-Pad10)") (class "Default")
      (node (ref "M1") (pin "10") (pinfunction "INT_10") (pintype "bidirectional"))
    )
    (net (code "59") (name "unconnected-(M1-WOL-Pad7)") (class "Default")
      (node (ref "M1") (pin "7") (pinfunction "WOL_7") (pintype "bidirectional"))
    )
    (net (code "60") (name "unconnected-(U$5-DS.1-PadJ1.5)") (class "Default")
      (node (ref "U$5") (pin "J1.5") (pinfunction "DS.1_J1.5") (pintype "bidirectional"))
    )
    (net (code "61") (name "unconnected-(U$5-DS.2-PadJ2.6)") (class "Default")
      (node (ref "U$5") (pin "J2.6") (pinfunction "DS.2_J2.6") (pintype "bidirectional"))
    )
    (net (code "62") (name "unconnected-(U$5-SCL.2-PadJ2.5)") (class "Default")
      (node (ref "U$5") (pin "J2.5") (pinfunction "SCL.2_J2.5") (pintype "bidirectional"))
    )
    (net (code "63") (name "unconnected-(U$5-SDA.2-PadJ2.4)") (class "Default")
      (node (ref "U$5") (pin "J2.4") (pinfunction "SDA.2_J2.4") (pintype "bidirectional"))
    )
    (net (code "64") (name "unconnected-(U$5-SQ-PadJ2.7)") (class "Default")
      (node (ref "U$5") (pin "J2.7") (pinfunction "SQ_J2.7") (pintype "bidirectional"))
    )
    (net (code "65") (name "unconnected-(U$16-SWCLOSE-PadSWCLOSED)") (class "Default")
      (node (ref "U$16") (pin "SWCLOSED") (pinfunction "SWCLOSE_SWCLOSED") (pintype "bidirectional"))
    )
    (net (code "66") (name "unconnected-(U$17-SWCLOSE-PadSWCLOSED)") (class "Default")
      (node (ref "U$17") (pin "SWCLOSED") (pinfunction "SWCLOSE_SWCLOSED") (pintype "bidirectional"))
    )
  )
)
